# jtag.net
KiCad netlist of a schematic drawn in Altium Designer
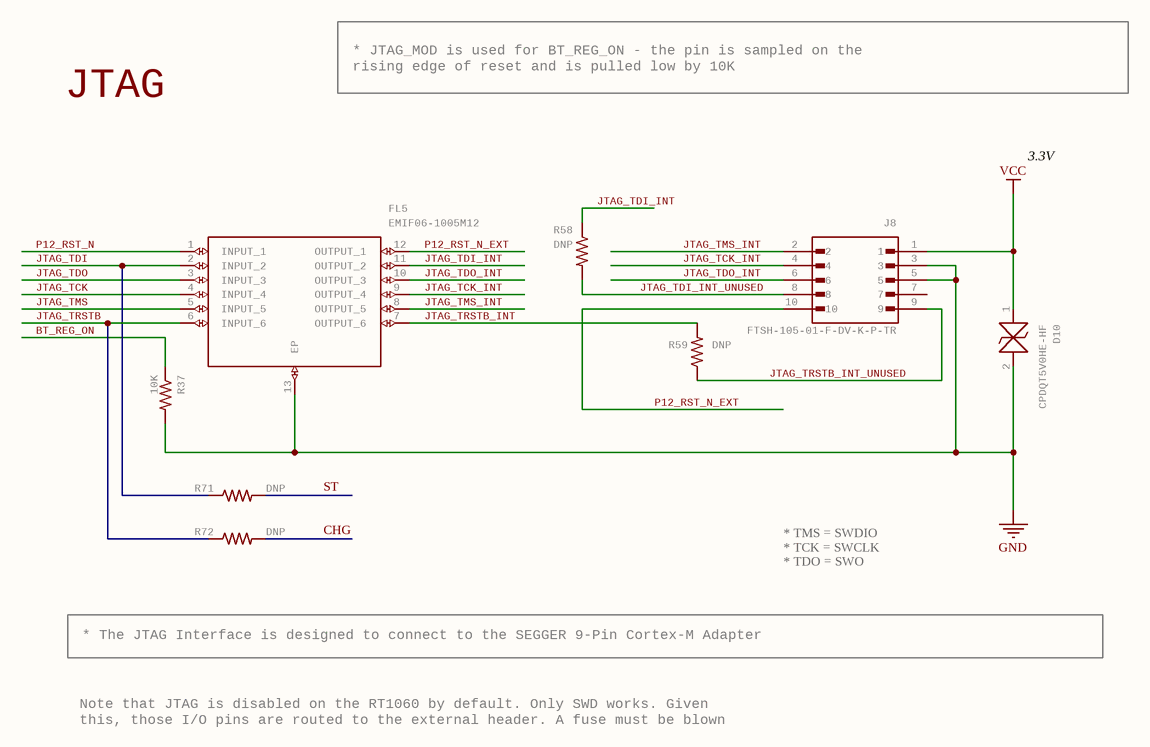
[diagram p0: jtag.SchDoc]

(export (version "E")
  (design (tool "Eeschema 10.0.6"))
  (components
    (comp (ref "D10")
      (value "CPDQT5V0HE-HF")
      (footprint "CPDQT5V0HEHF")
      (description "ESD Suppressors / TVS Diodes DIODE ESD 5VWM 65W 0402/SOD-923F   Source:  Datasheet")
      (fields (field (name "MOUSER_PART_NUMBER") "MOUSER_PART_NUMBER"))
      (libsource (lib "rt10") (part "CPDQT5V0HE-HF"))
    )
    (comp (ref "FL5")
      (value "EMIF06-1005M12")
      (footprint "SON40P150X250X65-13N")
      (description "EMI Filter Circuits 6lin lw cpcitnc EMI 45pF -35db @ 900MHz   Source:  Datasheet")
      (fields (field (name "MOUSER_PART_NUMBER") "511-EMIF06-1005M12"))
      (libsource (lib "rt10") (part "EMIF06-1005M12"))
    )
    (comp (ref "J8")
      (value "FTSH-105-01-F-DV-K-P-TR")
      (footprint "CNC_3221-10-0300-00")
      (description "Check availability")
      (fields (field (name "MF") "CNC Tech") (field (name "MP") " FTSH-105-01-F-DV-K-P-TR"))
      (libsource (lib "rt10") (part "3221-10-0300-00"))
    )
    (comp (ref "R37")
      (value "10K")
      (footprint "0402-RES")
      (description "ResistorBasic schematic elements and footprints for 0603, 1206, and PTH resistors.")
      (fields (field (name "MPN") "AC0402FR-1310KL"))
      (libsource (lib "rt10") (part "RESISTOR0402-RES"))
    )
    (comp (ref "R58")
      (value "DNP")
      (footprint "0402-RES")
      (description "ResistorBasic schematic elements and footprints for 0603, 1206, and PTH resistors.")
      (libsource (lib "rt10") (part "RESISTOR0402-RES"))
    )
    (comp (ref "R59")
      (value "DNP")
      (footprint "0402-RES")
      (description "ResistorBasic schematic elements and footprints for 0603, 1206, and PTH resistors.")
      (libsource (lib "rt10") (part "RESISTOR0402-RES"))
    )
    (comp (ref "R71")
      (value "DNP")
      (footprint "0402-RES")
      (description "ResistorBasic schematic elements and footprints for 0603, 1206, and PTH resistors.")
      (libsource (lib "rt10") (part "RESISTOR0402-RES"))
    )
    (comp (ref "R72")
      (value "DNP")
      (footprint "0402-RES")
      (description "ResistorBasic schematic elements and footprints for 0603, 1206, and PTH resistors.")
      (libsource (lib "rt10") (part "RESISTOR0402-RES"))
    )
  )
  (nets
    (net (code "1") (name "/BT_REG_ON") (class "Default")
      (node (ref "R37") (pin "1") (pinfunction "1_1") (pintype "passive"))
    )
    (net (code "2") (name "/CHG") (class "Default")
      (node (ref "R72") (pin "2") (pinfunction "2_2") (pintype "passive"))
    )
    (net (code "3") (name "/JTAG_TCK") (class "Default")
      (node (ref "FL5") (pin "4") (pinfunction "INPUT_4_4") (pintype "bidirectional"))
    )
    (net (code "4") (name "/JTAG_TCK_INT") (class "Default")
      (node (ref "FL5") (pin "9") (pinfunction "OUTPUT_4_9") (pintype "bidirectional"))
      (node (ref "J8") (pin "4") (pinfunction "4_4") (pintype "passive"))
    )
    (net (code "5") (name "/JTAG_TDI") (class "Default")
      (node (ref "FL5") (pin "2") (pinfunction "INPUT_2_2") (pintype "bidirectional"))
      (node (ref "R71") (pin "1") (pinfunction "1_1") (pintype "passive"))
    )
    (net (code "6") (name "/JTAG_TDI_INT") (class "Default")
      (node (ref "FL5") (pin "11") (pinfunction "OUTPUT_2_11") (pintype "bidirectional"))
      (node (ref "R58") (pin "1") (pinfunction "1_1") (pintype "passive"))
    )
    (net (code "7") (name "/JTAG_TDI_INT_UNUSED") (class "Default")
      (node (ref "J8") (pin "8") (pinfunction "8_8") (pintype "passive"))
      (node (ref "R58") (pin "2") (pinfunction "2_2") (pintype "passive"))
    )
    (net (code "8") (name "/JTAG_TDO") (class "Default")
      (node (ref "FL5") (pin "3") (pinfunction "INPUT_3_3") (pintype "bidirectional"))
    )
    (net (code "9") (name "/JTAG_TDO_INT") (class "Default")
      (node (ref "FL5") (pin "10") (pinfunction "OUTPUT_3_10") (pintype "bidirectional"))
      (node (ref "J8") (pin "6") (pinfunction "6_6") (pintype "passive"))
    )
    (net (code "10") (name "/JTAG_TMS") (class "Default")
      (node (ref "FL5") (pin "5") (pinfunction "INPUT_5_5") (pintype "bidirectional"))
    )
    (net (code "11") (name "/JTAG_TMS_INT") (class "Default")
      (node (ref "FL5") (pin "8") (pinfunction "OUTPUT_5_8") (pintype "bidirectional"))
      (node (ref "J8") (pin "2") (pinfunction "2_2") (pintype "passive"))
    )
    (net (code "12") (name "/JTAG_TRSTB") (class "Default")
      (node (ref "FL5") (pin "6") (pinfunction "INPUT_6_6") (pintype "bidirectional"))
      (node (ref "R72") (pin "1") (pinfunction "1_1") (pintype "passive"))
    )
    (net (code "13") (name "/JTAG_TRSTB_INT") (class "Default")
      (node (ref "FL5") (pin "7") (pinfunction "OUTPUT_6_7") (pintype "bidirectional"))
      (node (ref "R59") (pin "2") (pinfunction "2_2") (pintype "passive"))
    )
    (net (code "14") (name "/JTAG_TRSTB_INT_UNUSED") (class "Default")
      (node (ref "J8") (pin "9") (pinfunction "9_9") (pintype "passive"))
      (node (ref "R59") (pin "1") (pinfunction "1_1") (pintype "passive"))
    )
    (net (code "15") (name "/P12_RST_N") (class "Default")
      (node (ref "FL5") (pin "1") (pinfunction "INPUT_1_1") (pintype "bidirectional"))
    )
    (net (code "16") (name "/P12_RST_N_EXT") (class "Default")
      (node (ref "FL5") (pin "12") (pinfunction "OUTPUT_1_12") (pintype "bidirectional"))
      (node (ref "J8") (pin "10") (pinfunction "10_10") (pintype "passive"))
    )
    (net (code "17") (name "/ST") (class "Default")
      (node (ref "R71") (pin "2") (pinfunction "2_2") (pintype "passive"))
    )
    (net (code "18") (name "GND") (class "Default")
      (node (ref "D10") (pin "2") (pinfunction "2_2") (pintype "bidirectional"))
      (node (ref "FL5") (pin "13") (pinfunction "EP_13") (pintype "bidirectional"))
      (node (ref "J8") (pin "3") (pinfunction "3_3") (pintype "passive"))
      (node (ref "J8") (pin "5") (pinfunction "5_5") (pintype "passive"))
      (node (ref "R37") (pin "2") (pinfunction "2_2") (pintype "passive"))
    )
    (net (code "19") (name "VCC") (class "Default")
      (node (ref "D10") (pin "1") (pinfunction "1_1") (pintype "bidirectional"))
      (node (ref "J8") (pin "1") (pinfunction "1_1") (pintype "passive"))
    )
    (net (code "20") (name "unconnected-(J8-Pad7)") (class "Default")
      (node (ref "J8") (pin "7") (pinfunction "7_7") (pintype "passive"))
    )
  )
)
